# leddriverv2.net
KiCad netlist of a schematic drawn in EAGLE
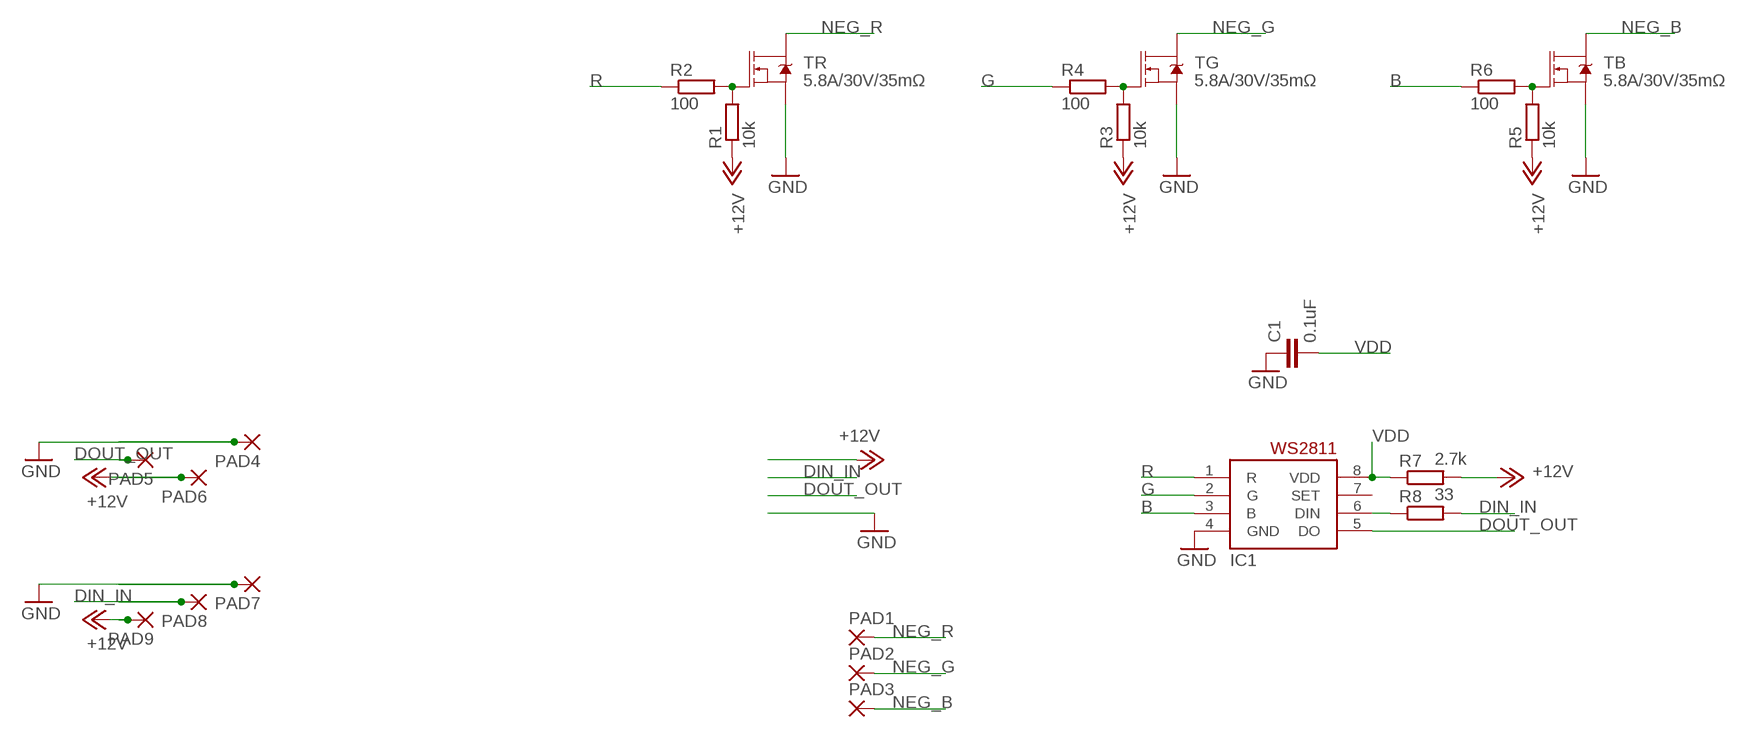
[diagram p0: schematic, sheet 1]

(export (version "E")
  (design (tool "Eeschema 10.0.6"))
  (components
    (comp (ref "C1")
      (value "0.1uF")
      (footprint "eagle-import:C1206")
      (libsource (lib "eagle-import") (part "C-EUC1206"))
    )
    (comp (ref "IC1")
      (value "WS2811-SOP8")
      (footprint "eagle-import:SO08-SKINNYPADS")
      (libsource (lib "eagle-import") (part "WS2811-SOP8"))
    )
    (comp (ref "PAD1")
      (value "3,81/1,4")
      (footprint "eagle-import:3,81_1,4")
      (libsource (lib "eagle-import") (part "3,81/1,4"))
    )
    (comp (ref "PAD2")
      (value "3,81/1,4")
      (footprint "eagle-import:3,81_1,4")
      (libsource (lib "eagle-import") (part "3,81/1,4"))
    )
    (comp (ref "PAD3")
      (value "3,81/1,4")
      (footprint "eagle-import:3,81_1,4")
      (libsource (lib "eagle-import") (part "3,81/1,4"))
    )
    (comp (ref "PAD4")
      (value "2,54/1,1")
      (footprint "eagle-import:2,54_1,1")
      (libsource (lib "eagle-import") (part "2,54/1,1"))
    )
    (comp (ref "PAD5")
      (value "2,54/1,1")
      (footprint "eagle-import:2,54_1,1")
      (libsource (lib "eagle-import") (part "2,54/1,1"))
    )
    (comp (ref "PAD6")
      (value "2,54/1,1")
      (footprint "eagle-import:2,54_1,1")
      (libsource (lib "eagle-import") (part "2,54/1,1"))
    )
    (comp (ref "PAD7")
      (value "2,54/1,1")
      (footprint "eagle-import:2,54_1,1")
      (libsource (lib "eagle-import") (part "2,54/1,1"))
    )
    (comp (ref "PAD8")
      (value "2,54/1,1")
      (footprint "eagle-import:2,54_1,1")
      (libsource (lib "eagle-import") (part "2,54/1,1"))
    )
    (comp (ref "PAD9")
      (value "2,54/1,1")
      (footprint "eagle-import:2,54_1,1")
      (libsource (lib "eagle-import") (part "2,54/1,1"))
    )
    (comp (ref "R1")
      (value "10k")
      (footprint "eagle-import:R0805")
      (libsource (lib "eagle-import") (part "R-EU_R0805"))
    )
    (comp (ref "R2")
      (value "100")
      (footprint "eagle-import:R0805")
      (libsource (lib "eagle-import") (part "R-EU_R0805"))
    )
    (comp (ref "R3")
      (value "10k")
      (footprint "eagle-import:R0805")
      (libsource (lib "eagle-import") (part "R-EU_R0805"))
    )
    (comp (ref "R4")
      (value "100")
      (footprint "eagle-import:R0805")
      (libsource (lib "eagle-import") (part "R-EU_R0805"))
    )
    (comp (ref "R5")
      (value "10k")
      (footprint "eagle-import:R0805")
      (libsource (lib "eagle-import") (part "R-EU_R0805"))
    )
    (comp (ref "R6")
      (value "100")
      (footprint "eagle-import:R0805")
      (libsource (lib "eagle-import") (part "R-EU_R0805"))
    )
    (comp (ref "R7")
      (value "2.7k")
      (footprint "eagle-import:R0805")
      (libsource (lib "eagle-import") (part "R-EU_R0805"))
    )
    (comp (ref "R8")
      (value "33")
      (footprint "eagle-import:R0805")
      (libsource (lib "eagle-import") (part "R-EU_R0805"))
    )
    (comp (ref "TB")
      (value "5.8A/30V/35mΩ")
      (footprint "eagle-import:SOT23-3")
      (libsource (lib "eagle-import") (part "MOSFET-NCH-AO3404A"))
    )
    (comp (ref "TG")
      (value "5.8A/30V/35mΩ")
      (footprint "eagle-import:SOT23-3")
      (libsource (lib "eagle-import") (part "MOSFET-NCH-AO3404A"))
    )
    (comp (ref "TR")
      (value "5.8A/30V/35mΩ")
      (footprint "eagle-import:SOT23-3")
      (libsource (lib "eagle-import") (part "MOSFET-NCH-AO3404A"))
    )
  )
  (nets
    (net (code "1") (name "+12V") (class "Default")
      (node (ref "PAD6") (pin "1") (pinfunction "P_1") (pintype "passive"))
      (node (ref "PAD9") (pin "1") (pinfunction "P_1") (pintype "passive"))
      (node (ref "R1") (pin "1") (pinfunction "1_1") (pintype "passive"))
      (node (ref "R3") (pin "1") (pinfunction "1_1") (pintype "passive"))
      (node (ref "R5") (pin "1") (pinfunction "1_1") (pintype "passive"))
      (node (ref "R7") (pin "2") (pinfunction "2_2") (pintype "passive"))
    )
    (net (code "2") (name "/B") (class "Default")
      (node (ref "IC1") (pin "3") (pinfunction "B_3") (pintype "open_collector"))
      (node (ref "R6") (pin "1") (pinfunction "1_1") (pintype "passive"))
    )
    (net (code "3") (name "/DIN_IN") (class "Default")
      (node (ref "PAD8") (pin "1") (pinfunction "P_1") (pintype "passive"))
      (node (ref "R8") (pin "2") (pinfunction "2_2") (pintype "passive"))
    )
    (net (code "4") (name "/DOUT_OUT") (class "Default")
      (node (ref "IC1") (pin "5") (pinfunction "DO_5") (pintype "output"))
      (node (ref "PAD5") (pin "1") (pinfunction "P_1") (pintype "passive"))
    )
    (net (code "5") (name "/G") (class "Default")
      (node (ref "IC1") (pin "2") (pinfunction "G_2") (pintype "open_collector"))
      (node (ref "R4") (pin "1") (pinfunction "1_1") (pintype "passive"))
    )
    (net (code "6") (name "/NEG_B") (class "Default")
      (node (ref "PAD3") (pin "1") (pinfunction "P_1") (pintype "passive"))
      (node (ref "TB") (pin "3") (pinfunction "D_3") (pintype "bidirectional"))
    )
    (net (code "7") (name "/NEG_G") (class "Default")
      (node (ref "PAD2") (pin "1") (pinfunction "P_1") (pintype "passive"))
      (node (ref "TG") (pin "3") (pinfunction "D_3") (pintype "bidirectional"))
    )
    (net (code "8") (name "/NEG_R") (class "Default")
      (node (ref "PAD1") (pin "1") (pinfunction "P_1") (pintype "passive"))
      (node (ref "TR") (pin "3") (pinfunction "D_3") (pintype "bidirectional"))
    )
    (net (code "9") (name "/R") (class "Default")
      (node (ref "IC1") (pin "1") (pinfunction "R_1") (pintype "open_collector"))
      (node (ref "R2") (pin "1") (pinfunction "1_1") (pintype "passive"))
    )
    (net (code "10") (name "/VDD") (class "Default")
      (node (ref "C1") (pin "2") (pinfunction "2_2") (pintype "passive"))
      (node (ref "IC1") (pin "8") (pinfunction "VDD_8") (pintype "power_in"))
      (node (ref "R7") (pin "1") (pinfunction "1_1") (pintype "passive"))
    )
    (net (code "11") (name "GND") (class "Default")
      (node (ref "C1") (pin "1") (pinfunction "1_1") (pintype "passive"))
      (node (ref "IC1") (pin "4") (pinfunction "GND_4") (pintype "power_in"))
      (node (ref "PAD4") (pin "1") (pinfunction "P_1") (pintype "passive"))
      (node (ref "PAD7") (pin "1") (pinfunction "P_1") (pintype "passive"))
      (node (ref "TB") (pin "2") (pinfunction "S_2") (pintype "bidirectional"))
      (node (ref "TG") (pin "2") (pinfunction "S_2") (pintype "bidirectional"))
      (node (ref "TR") (pin "2") (pinfunction "S_2") (pintype "bidirectional"))
    )
    (net (code "12") (name "Net-(IC1-DIN)") (class "Default")
      (node (ref "IC1") (pin "6") (pinfunction "DIN_6") (pintype "input"))
      (node (ref "R8") (pin "1") (pinfunction "1_1") (pintype "passive"))
    )
    (net (code "13") (name "Net-(TB-G)") (class "Default")
      (node (ref "R5") (pin "2") (pinfunction "2_2") (pintype "passive"))
      (node (ref "R6") (pin "2") (pinfunction "2_2") (pintype "passive"))
      (node (ref "TB") (pin "1") (pinfunction "G_1") (pintype "bidirectional"))
    )
    (net (code "14") (name "Net-(TG-G)") (class "Default")
      (node (ref "R3") (pin "2") (pinfunction "2_2") (pintype "passive"))
      (node (ref "R4") (pin "2") (pinfunction "2_2") (pintype "passive"))
      (node (ref "TG") (pin "1") (pinfunction "G_1") (pintype "bidirectional"))
    )
    (net (code "15") (name "Net-(TR-G)") (class "Default")
      (node (ref "R1") (pin "2") (pinfunction "2_2") (pintype "passive"))
      (node (ref "R2") (pin "2") (pinfunction "2_2") (pintype "passive"))
      (node (ref "TR") (pin "1") (pinfunction "G_1") (pintype "bidirectional"))
    )
    (net (code "16") (name "unconnected-(IC1-SET-Pad7)") (class "Default")
      (node (ref "IC1") (pin "7") (pinfunction "SET_7") (pintype "input"))
    )
  )
)
